# VCU_Schematic.net
KiCad netlist of a schematic drawn in Altium Designer
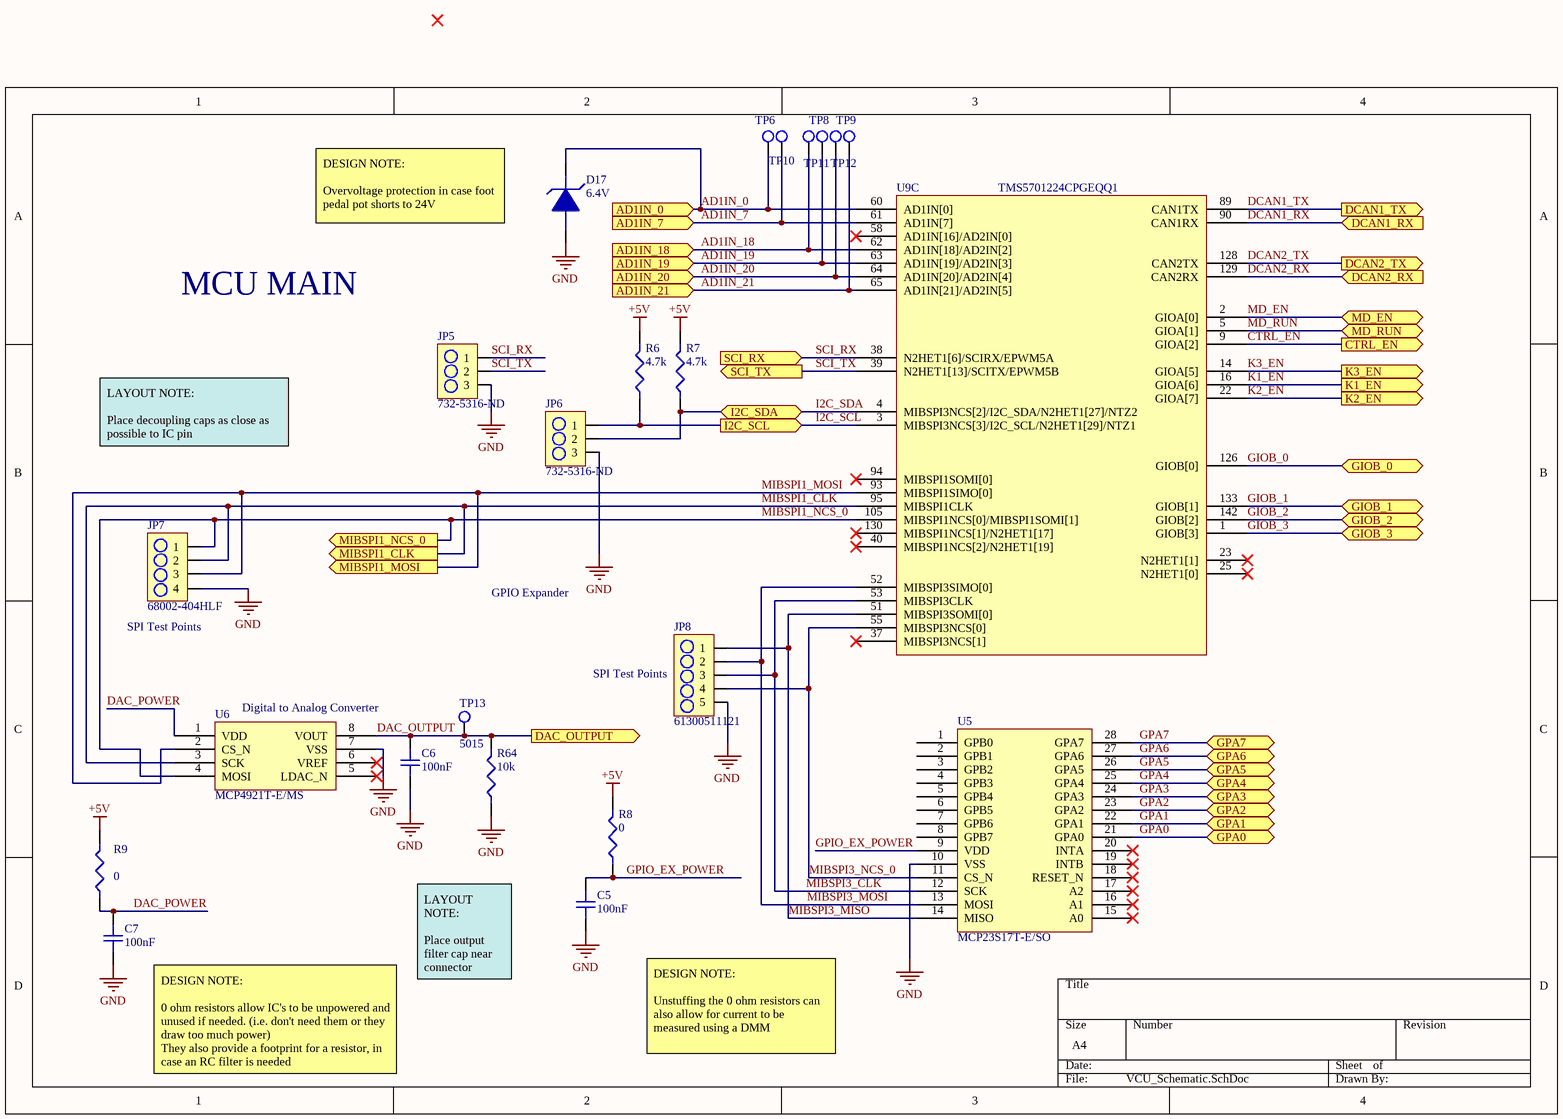
[diagram p0: VCU_Schematic.SchDoc]

(export (version "E")
  (design (tool "Eeschema 10.0.6"))
  (components
    (comp (ref "C5")
      (value "100nF")
      (footprint "PHANTOM_FOOTPRINTS:C0805")
      (description "CAP MLCC 100nF 10Volts U2J 5%")
      (fields
        (field (name "MANUFACTURER") "Murata")
        (field (name "MANUFACTURER PART NUMBER") "GRM21B7U1A104JA01L")
      )
      (libsource (lib "PHANTOM_LIBRARY") (part "GRM21B7U1A104JA01L"))
    )
    (comp (ref "C6")
      (value "100nF")
      (footprint "PHANTOM_FOOTPRINTS:C0805")
      (description "CAP MLCC 100nF 10Volts U2J 5%")
      (fields
        (field (name "MANUFACTURER") "Murata")
        (field (name "MANUFACTURER PART NUMBER") "GRM21B7U1A104JA01L")
      )
      (libsource (lib "PHANTOM_LIBRARY") (part "GRM21B7U1A104JA01L"))
    )
    (comp (ref "C7")
      (value "100nF")
      (footprint "PHANTOM_FOOTPRINTS:C0805")
      (description "CAP MLCC 100nF 10Volts U2J 5%")
      (fields
        (field (name "MANUFACTURER") "Murata")
        (field (name "MANUFACTURER PART NUMBER") "GRM21B7U1A104JA01L")
      )
      (libsource (lib "PHANTOM_LIBRARY") (part "GRM21B7U1A104JA01L"))
    )
    (comp (ref "D17")
      (value "6.4V")
      (footprint "DIODE_TVS")
      (description "DIODE TVS_6V4 5VWM 9.2VC SMA")
      (fields (field (name "MANUFACTURER") "Littelfuse") (field (name "MANUFACTURER PART NUMBER") "SMAJ5.0A"))
      (libsource (lib "PHANTOM_LIBRARY") (part "SMAJ5.0A"))
    )
    (comp (ref "JP5")
      (value "732-5316-ND")
      (footprint "3PIN_HEADER")
      (fields
        (field (name "MANUFACTURER") "Wurth Electronics")
        (field (name "MANUFACTURER PART NUMBER") "61300311121")
      )
      (libsource (lib "PHANTOM_LIBRARY") (part "61300311121"))
    )
    (comp (ref "JP6")
      (value "732-5316-ND")
      (footprint "3PIN_HEADER")
      (fields
        (field (name "MANUFACTURER") "Wurth Electronics")
        (field (name "MANUFACTURER PART NUMBER") "61300311121")
      )
      (libsource (lib "PHANTOM_LIBRARY") (part "61300311121"))
    )
    (comp (ref "JP7")
      (value "68002-404HLF")
      (footprint "4PIN_HEADER")
      (description "CONN_HeaderPins4pos 4 Positions Header, Unshrouded Connector 0.100\" (2.54mm) Through Hole Tin")
      (fields (field (name "MANUFACTURER") "Amphenol FCI"))
      (libsource (lib "PHANTOM_LIBRARY") (part "68002-404HLF"))
    )
    (comp (ref "JP8")
      (value "61300511121")
      (footprint "5PIN_HEADER")
      (fields (field (name "MANUFACTURER") "Wurth Electronics"))
      (libsource (lib "PHANTOM_LIBRARY") (part "61300511121"))
    )
    (comp (ref "R6")
      (value "4.7k")
      (footprint "R0805")
      (description "RES SMD 4.7K OHM 1% 1/8W 0805")
      (fields
        (field (name "MANUFACTURER") "Yageo")
        (field (name "MANUFACTURER PART NUMBER") "RC0805FR-074K7L")
      )
      (libsource (lib "PHANTOM_LIBRARY") (part "RC0805FR-074K7L"))
    )
    (comp (ref "R7")
      (value "4.7k")
      (footprint "R0805")
      (description "RES SMD 4.7K OHM 1% 1/8W 0805")
      (fields
        (field (name "MANUFACTURER") "Yageo")
        (field (name "MANUFACTURER PART NUMBER") "RC0805FR-074K7L")
      )
      (libsource (lib "PHANTOM_LIBRARY") (part "RC0805FR-074K7L"))
    )
    (comp (ref "R8")
      (value "0")
      (footprint "R0805")
      (description "RES SMD 0 OHM 1/8W 0805")
      (fields
        (field (name "MANUFACTURER") "Yageo")
        (field (name "MANUFACTURER PART NUMBER") "RC0805JR-070RL")
      )
      (libsource (lib "PHANTOM_LIBRARY") (part "RC0805JR-070RL"))
    )
    (comp (ref "R9")
      (value "0")
      (footprint "R0805")
      (description "RES SMD 0 OHM 1/8W 0805")
      (fields
        (field (name "MANUFACTURER") "Yageo")
        (field (name "MANUFACTURER PART NUMBER") "RC0805JR-070RL")
      )
      (libsource (lib "PHANTOM_LIBRARY") (part "RC0805JR-070RL"))
    )
    (comp (ref "R64")
      (value "10k")
      (footprint "R0805")
      (description "RES SMD 10K OHM 1% 1/8W 0805")
      (fields
        (field (name "MANUFACTURER") "Yageo Phycomp")
        (field (name "MANUFACTURER PART NUMBER") "RC0805FR-071KL")
      )
      (libsource (lib "PHANTOM_LIBRARY") (part "RC0805FR-071KL"))
    )
    (comp (ref "TP6")
      (value "5015")
      (footprint "TP_HOOK")
      (description "TEST POINT, PCB, SMT")
      (fields (field (name "MANUFACTURER") "Keystone Electronics"))
      (libsource (lib "PHANTOM_LIBRARY") (part "5015"))
    )
    (comp (ref "TP8")
      (value "5015")
      (footprint "TP_HOOK")
      (description "TEST POINT, PCB, SMT")
      (fields (field (name "MANUFACTURER") "Keystone Electronics"))
      (libsource (lib "PHANTOM_LIBRARY") (part "5015"))
    )
    (comp (ref "TP9")
      (value "5015")
      (footprint "TP_HOOK")
      (description "TEST POINT, PCB, SMT")
      (fields (field (name "MANUFACTURER") "Keystone Electronics"))
      (libsource (lib "PHANTOM_LIBRARY") (part "5015"))
    )
    (comp (ref "TP10")
      (value "5015")
      (footprint "TP_HOOK")
      (description "TEST POINT, PCB, SMT")
      (fields (field (name "MANUFACTURER") "Keystone Electronics"))
      (libsource (lib "PHANTOM_LIBRARY") (part "5015"))
    )
    (comp (ref "TP11")
      (value "5015")
      (footprint "TP_HOOK")
      (description "TEST POINT, PCB, SMT")
      (fields (field (name "MANUFACTURER") "Keystone Electronics"))
      (libsource (lib "PHANTOM_LIBRARY") (part "5015"))
    )
    (comp (ref "TP12")
      (value "5015")
      (footprint "TP_HOOK")
      (description "TEST POINT, PCB, SMT")
      (fields (field (name "MANUFACTURER") "Keystone Electronics"))
      (libsource (lib "PHANTOM_LIBRARY") (part "5015"))
    )
    (comp (ref "TP13")
      (value "5015")
      (footprint "TP_HOOK")
      (description "TEST POINT, PCB, SMT")
      (fields (field (name "MANUFACTURER") "Keystone Electronics"))
      (libsource (lib "PHANTOM_LIBRARY") (part "5015"))
    )
    (comp (ref "U5")
      (value "MCP23S17T-E/SO")
      (footprint "28-SOIC_MCP23S17")
      (description "IC I/O Expander, 16bit, 10 MHz, SPI, 4.5 V, 5.5 V, SOIC")
      (fields (field (name "MANUFACTURER") "Microchip"))
      (libsource (lib "PHANTOM_LIBRARY") (part "MCP23S17T-E/SO"))
    )
    (comp (ref "U6")
      (value "MCP4921T-E/MS")
      (footprint "8-MSOP_MCP4921")
      (description "IC Digital to Analog Converters - DAC Sgl 12-bit SPI int")
      (fields (field (name "MANUFACTURER") "Microchip"))
      (libsource (lib "PHANTOM_LIBRARY") (part "MCP4921T-E/MS"))
    )
    (comp (ref "U9")
      (value "TMS5701224CPGEQQ1")
      (footprint "LQFP-144")
      (description "ARM CORTEX R4 LOCK STEP HERCULES MCU")
      (fields (field (name "MANUFACTURER") "Texas Instruments"))
      (libsource (lib "PHANTOM_LIBRARY") (part "TMS5701224CPGEQQ1"))
    )
  )
  (nets
    (net (code "1") (name "+5V") (class "Default")
      (node (ref "R6") (pin "2") (pinfunction "2_2") (pintype "passive"))
      (node (ref "R7") (pin "2") (pinfunction "2_2") (pintype "passive"))
      (node (ref "R8") (pin "2") (pinfunction "2_2") (pintype "passive"))
      (node (ref "R9") (pin "2") (pinfunction "2_2") (pintype "passive"))
    )
    (net (code "2") (name "/AD1IN_0") (class "Default")
      (node (ref "D17") (pin "1") (pinfunction "1_1") (pintype "passive"))
      (node (ref "TP6") (pin "1") (pinfunction "1_1") (pintype "passive"))
      (node (ref "U9") (pin "60") (pinfunction "AD1IN[0]_60") (pintype "passive"))
    )
    (net (code "3") (name "/AD1IN_7") (class "Default")
      (node (ref "TP10") (pin "1") (pinfunction "1_1") (pintype "passive"))
      (node (ref "U9") (pin "61") (pinfunction "AD1IN[7]_61") (pintype "passive"))
    )
    (net (code "4") (name "/AD1IN_18") (class "Default")
      (node (ref "TP11") (pin "1") (pinfunction "1_1") (pintype "passive"))
      (node (ref "U9") (pin "62") (pinfunction "AD1IN[18]/AD2IN[2]_62") (pintype "passive"))
    )
    (net (code "5") (name "/AD1IN_19") (class "Default")
      (node (ref "TP8") (pin "1") (pinfunction "1_1") (pintype "passive"))
      (node (ref "U9") (pin "63") (pinfunction "AD1IN[19]/AD2IN[3]_63") (pintype "passive"))
    )
    (net (code "6") (name "/AD1IN_20") (class "Default")
      (node (ref "TP12") (pin "1") (pinfunction "1_1") (pintype "passive"))
      (node (ref "U9") (pin "64") (pinfunction "AD1IN[20]/AD2IN[4]_64") (pintype "passive"))
    )
    (net (code "7") (name "/AD1IN_21") (class "Default")
      (node (ref "TP9") (pin "1") (pinfunction "1_1") (pintype "passive"))
      (node (ref "U9") (pin "65") (pinfunction "AD1IN[21]/AD2IN[5]_65") (pintype "passive"))
    )
    (net (code "8") (name "/CTRL_EN") (class "Default")
      (node (ref "U9") (pin "9") (pinfunction "GIOA[2]_9") (pintype "passive"))
    )
    (net (code "9") (name "/DAC_OUTPUT") (class "Default")
      (node (ref "C6") (pin "2") (pinfunction "2_2") (pintype "passive"))
      (node (ref "R64") (pin "2") (pinfunction "2_2") (pintype "passive"))
      (node (ref "TP13") (pin "1") (pinfunction "1_1") (pintype "passive"))
      (node (ref "U6") (pin "8") (pinfunction "VOUT_8") (pintype "passive"))
    )
    (net (code "10") (name "/DAC_POWER") (class "Default")
      (node (ref "C7") (pin "2") (pinfunction "2_2") (pintype "passive"))
      (node (ref "R9") (pin "1") (pinfunction "1_1") (pintype "passive"))
      (node (ref "U6") (pin "1") (pinfunction "VDD_1") (pintype "passive"))
    )
    (net (code "11") (name "/DCAN1_RX") (class "Default")
      (node (ref "U9") (pin "90") (pinfunction "CAN1RX_90") (pintype "passive"))
    )
    (net (code "12") (name "/DCAN1_TX") (class "Default")
      (node (ref "U9") (pin "89") (pinfunction "CAN1TX_89") (pintype "passive"))
    )
    (net (code "13") (name "/DCAN2_RX") (class "Default")
      (node (ref "U9") (pin "129") (pinfunction "CAN2RX_129") (pintype "passive"))
    )
    (net (code "14") (name "/DCAN2_TX") (class "Default")
      (node (ref "U9") (pin "128") (pinfunction "CAN2TX_128") (pintype "passive"))
    )
    (net (code "15") (name "/GIOB_0") (class "Default")
      (node (ref "U9") (pin "126") (pinfunction "GIOB[0]_126") (pintype "passive"))
    )
    (net (code "16") (name "/GIOB_1") (class "Default")
      (node (ref "U9") (pin "133") (pinfunction "GIOB[1]_133") (pintype "passive"))
    )
    (net (code "17") (name "/GIOB_2") (class "Default")
      (node (ref "U9") (pin "142") (pinfunction "GIOB[2]_142") (pintype "passive"))
    )
    (net (code "18") (name "/GIOB_3") (class "Default")
      (node (ref "U9") (pin "1") (pinfunction "GIOB[3]_1") (pintype "passive"))
    )
    (net (code "19") (name "/GPA0") (class "Default")
      (node (ref "U5") (pin "21") (pinfunction "GPA0_21") (pintype "passive"))
    )
    (net (code "20") (name "/GPA1") (class "Default")
      (node (ref "U5") (pin "22") (pinfunction "GPA1_22") (pintype "passive"))
    )
    (net (code "21") (name "/GPA2") (class "Default")
      (node (ref "U5") (pin "23") (pinfunction "GPA2_23") (pintype "passive"))
    )
    (net (code "22") (name "/GPA3") (class "Default")
      (node (ref "U5") (pin "24") (pinfunction "GPA3_24") (pintype "passive"))
    )
    (net (code "23") (name "/GPA4") (class "Default")
      (node (ref "U5") (pin "25") (pinfunction "GPA4_25") (pintype "passive"))
    )
    (net (code "24") (name "/GPA5") (class "Default")
      (node (ref "U5") (pin "26") (pinfunction "GPA5_26") (pintype "passive"))
    )
    (net (code "25") (name "/GPA6") (class "Default")
      (node (ref "U5") (pin "27") (pinfunction "GPA6_27") (pintype "passive"))
    )
    (net (code "26") (name "/GPA7") (class "Default")
      (node (ref "U5") (pin "28") (pinfunction "GPA7_28") (pintype "passive"))
    )
    (net (code "27") (name "/GPIO_EX_POWER") (class "Default")
      (node (ref "C5") (pin "2") (pinfunction "2_2") (pintype "passive"))
      (node (ref "R8") (pin "1") (pinfunction "1_1") (pintype "passive"))
      (node (ref "U5") (pin "9") (pinfunction "VDD_9") (pintype "passive"))
    )
    (net (code "28") (name "/I2C_SCL") (class "Default")
      (node (ref "JP6") (pin "1") (pinfunction "1_1") (pintype "passive"))
      (node (ref "R6") (pin "1") (pinfunction "1_1") (pintype "passive"))
      (node (ref "U9") (pin "3") (pinfunction "MIBSPI3NCS[3]/I2C_SCL/N2HET1[29]/NTZ1_3") (pintype "passive"))
    )
    (net (code "29") (name "/I2C_SDA") (class "Default")
      (node (ref "JP6") (pin "2") (pinfunction "2_2") (pintype "passive"))
      (node (ref "R7") (pin "1") (pinfunction "1_1") (pintype "passive"))
      (node (ref "U9") (pin "4") (pinfunction "MIBSPI3NCS[2]/I2C_SDA/N2HET1[27]/NTZ2_4") (pintype "passive"))
    )
    (net (code "30") (name "/K1_EN") (class "Default")
      (node (ref "U9") (pin "16") (pinfunction "GIOA[6]_16") (pintype "passive"))
    )
    (net (code "31") (name "/K2_EN") (class "Default")
      (node (ref "U9") (pin "22") (pinfunction "GIOA[7]_22") (pintype "passive"))
    )
    (net (code "32") (name "/K3_EN") (class "Default")
      (node (ref "U9") (pin "14") (pinfunction "GIOA[5]_14") (pintype "passive"))
    )
    (net (code "33") (name "/MD_EN") (class "Default")
      (node (ref "U9") (pin "2") (pinfunction "GIOA[0]_2") (pintype "passive"))
    )
    (net (code "34") (name "/MD_RUN") (class "Default")
      (node (ref "U9") (pin "5") (pinfunction "GIOA[1]_5") (pintype "passive"))
    )
    (net (code "35") (name "/MIBSPI1_CLK") (class "Default")
      (node (ref "JP7") (pin "2") (pinfunction "2_2") (pintype "passive"))
      (node (ref "U6") (pin "3") (pinfunction "SCK_3") (pintype "passive"))
      (node (ref "U9") (pin "95") (pinfunction "MIBSPI1CLK_95") (pintype "passive"))
    )
    (net (code "36") (name "/MIBSPI1_MOSI") (class "Default")
      (node (ref "JP7") (pin "3") (pinfunction "3_3") (pintype "passive"))
      (node (ref "U6") (pin "2") (pinfunction "CS_N_2") (pintype "passive"))
      (node (ref "U9") (pin "93") (pinfunction "MIBSPI1SIMO[0]_93") (pintype "passive"))
    )
    (net (code "37") (name "/MIBSPI1_NCS_0") (class "Default")
      (node (ref "JP7") (pin "1") (pinfunction "1_1") (pintype "passive"))
      (node (ref "U6") (pin "4") (pinfunction "MOSI_4") (pintype "passive"))
      (node (ref "U9") (pin "105") (pinfunction "MIBSPI1NCS[0]/MIBSPI1SOMI[1]_105") (pintype "passive"))
    )
    (net (code "38") (name "/MIBSPI3_CLK") (class "Default")
      (node (ref "JP8") (pin "3") (pinfunction "3_3") (pintype "passive"))
      (node (ref "U5") (pin "12") (pinfunction "SCK_12") (pintype "passive"))
      (node (ref "U9") (pin "53") (pinfunction "MIBSPI3CLK_53") (pintype "passive"))
    )
    (net (code "39") (name "/MIBSPI3_MISO") (class "Default")
      (node (ref "JP8") (pin "1") (pinfunction "1_1") (pintype "passive"))
      (node (ref "U5") (pin "14") (pinfunction "MISO_14") (pintype "passive"))
      (node (ref "U9") (pin "51") (pinfunction "MIBSPI3SOMI[0]_51") (pintype "passive"))
    )
    (net (code "40") (name "/MIBSPI3_MOSI") (class "Default")
      (node (ref "JP8") (pin "2") (pinfunction "2_2") (pintype "passive"))
      (node (ref "U5") (pin "13") (pinfunction "MOSI_13") (pintype "passive"))
      (node (ref "U9") (pin "52") (pinfunction "MIBSPI3SIMO[0]_52") (pintype "passive"))
    )
    (net (code "41") (name "/MIBSPI3_NCS_0") (class "Default")
      (node (ref "JP8") (pin "4") (pinfunction "4_4") (pintype "passive"))
      (node (ref "U5") (pin "11") (pinfunction "CS_N_11") (pintype "passive"))
      (node (ref "U9") (pin "55") (pinfunction "MIBSPI3NCS[0]_55") (pintype "passive"))
    )
    (net (code "42") (name "/SCI_RX") (class "Default")
      (node (ref "JP5") (pin "1") (pinfunction "1_1") (pintype "passive"))
      (node (ref "U9") (pin "38") (pinfunction "N2HET1[6]/SCIRX/EPWM5A_38") (pintype "passive"))
    )
    (net (code "43") (name "/SCI_TX") (class "Default")
      (node (ref "JP5") (pin "2") (pinfunction "2_2") (pintype "passive"))
      (node (ref "U9") (pin "39") (pinfunction "N2HET1[13]/SCITX/EPWM5B_39") (pintype "passive"))
    )
    (net (code "44") (name "GND") (class "Default")
      (node (ref "C5") (pin "1") (pinfunction "1_1") (pintype "passive"))
      (node (ref "C6") (pin "1") (pinfunction "1_1") (pintype "passive"))
      (node (ref "C7") (pin "1") (pinfunction "1_1") (pintype "passive"))
      (node (ref "D17") (pin "2") (pinfunction "2_2") (pintype "passive"))
      (node (ref "JP5") (pin "3") (pinfunction "3_3") (pintype "passive"))
      (node (ref "JP6") (pin "3") (pinfunction "3_3") (pintype "passive"))
      (node (ref "JP7") (pin "4") (pinfunction "4_4") (pintype "passive"))
      (node (ref "JP8") (pin "5") (pinfunction "5_5") (pintype "passive"))
      (node (ref "R64") (pin "1") (pinfunction "1_1") (pintype "passive"))
      (node (ref "U5") (pin "10") (pinfunction "VSS_10") (pintype "passive"))
      (node (ref "U6") (pin "7") (pinfunction "VSS_7") (pintype "passive"))
    )
    (net (code "45") (name "unconnected-(U5-A0-Pad15)") (class "Default")
      (node (ref "U5") (pin "15") (pinfunction "A0_15") (pintype "passive+no_connect"))
    )
    (net (code "46") (name "unconnected-(U5-A1-Pad16)") (class "Default")
      (node (ref "U5") (pin "16") (pinfunction "A1_16") (pintype "passive+no_connect"))
    )
    (net (code "47") (name "unconnected-(U5-A2-Pad17)") (class "Default")
      (node (ref "U5") (pin "17") (pinfunction "A2_17") (pintype "passive+no_connect"))
    )
    (net (code "48") (name "unconnected-(U5-GPB0-Pad1)") (class "Default")
      (node (ref "U5") (pin "1") (pinfunction "GPB0_1") (pintype "passive"))
    )
    (net (code "49") (name "unconnected-(U5-GPB1-Pad2)") (class "Default")
      (node (ref "U5") (pin "2") (pinfunction "GPB1_2") (pintype "passive"))
    )
    (net (code "50") (name "unconnected-(U5-GPB2-Pad3)") (class "Default")
      (node (ref "U5") (pin "3") (pinfunction "GPB2_3") (pintype "passive"))
    )
    (net (code "51") (name "unconnected-(U5-GPB3-Pad4)") (class "Default")
      (node (ref "U5") (pin "4") (pinfunction "GPB3_4") (pintype "passive"))
    )
    (net (code "52") (name "unconnected-(U5-GPB4-Pad5)") (class "Default")
      (node (ref "U5") (pin "5") (pinfunction "GPB4_5") (pintype "passive"))
    )
    (net (code "53") (name "unconnected-(U5-GPB5-Pad6)") (class "Default")
      (node (ref "U5") (pin "6") (pinfunction "GPB5_6") (pintype "passive"))
    )
    (net (code "54") (name "unconnected-(U5-GPB6-Pad7)") (class "Default")
      (node (ref "U5") (pin "7") (pinfunction "GPB6_7") (pintype "passive"))
    )
    (net (code "55") (name "unconnected-(U5-GPB7-Pad8)") (class "Default")
      (node (ref "U5") (pin "8") (pinfunction "GPB7_8") (pintype "passive"))
    )
    (net (code "56") (name "unconnected-(U5-INTA-Pad20)") (class "Default")
      (node (ref "U5") (pin "20") (pinfunction "INTA_20") (pintype "passive+no_connect"))
    )
    (net (code "57") (name "unconnected-(U5-INTB-Pad19)") (class "Default")
      (node (ref "U5") (pin "19") (pinfunction "INTB_19") (pintype "passive+no_connect"))
    )
    (net (code "58") (name "unconnected-(U5-RESET_N-Pad18)") (class "Default")
      (node (ref "U5") (pin "18") (pinfunction "RESET_N_18") (pintype "passive+no_connect"))
    )
    (net (code "59") (name "unconnected-(U6-LDAC_N-Pad5)") (class "Default")
      (node (ref "U6") (pin "5") (pinfunction "LDAC_N_5") (pintype "passive+no_connect"))
    )
    (net (code "60") (name "unconnected-(U6-VREF-Pad6)") (class "Default")
      (node (ref "U6") (pin "6") (pinfunction "VREF_6") (pintype "passive+no_connect"))
    )
    (net (code "61") (name "unconnected-(U9C-AD1IN[16]{slash}AD2IN[0]-Pad58)") (class "Default")
      (node (ref "U9") (pin "58") (pinfunction "AD1IN[16]/AD2IN[0]_58") (pintype "passive+no_connect"))
    )
    (net (code "62") (name "unconnected-(U9C-MIBSPI1NCS[1]{slash}N2HET1[17]-Pad130)") (class "Default")
      (node (ref "U9") (pin "130") (pinfunction "MIBSPI1NCS[1]/N2HET1[17]_130") (pintype "passive+no_connect"))
    )
    (net (code "63") (name "unconnected-(U9C-MIBSPI1NCS[2]{slash}N2HET1[19]-Pad40)") (class "Default")
      (node (ref "U9") (pin "40") (pinfunction "MIBSPI1NCS[2]/N2HET1[19]_40") (pintype "passive+no_connect"))
    )
    (net (code "64") (name "unconnected-(U9C-MIBSPI1SOMI[0]-Pad94)") (class "Default")
      (node (ref "U9") (pin "94") (pinfunction "MIBSPI1SOMI[0]_94") (pintype "passive+no_connect"))
    )
    (net (code "65") (name "unconnected-(U9C-MIBSPI3NCS[1]-Pad37)") (class "Default")
      (node (ref "U9") (pin "37") (pinfunction "MIBSPI3NCS[1]_37") (pintype "passive+no_connect"))
    )
    (net (code "66") (name "unconnected-(U9C-N2HET1[0]-Pad25)") (class "Default")
      (node (ref "U9") (pin "25") (pinfunction "N2HET1[0]_25") (pintype "passive+no_connect"))
    )
    (net (code "67") (name "unconnected-(U9C-N2HET1[1]-Pad23)") (class "Default")
      (node (ref "U9") (pin "23") (pinfunction "N2HET1[1]_23") (pintype "passive+no_connect"))
    )
  )
)
